# led_board_robot_vs_v2.net
KiCad netlist of a schematic drawn in EAGLE
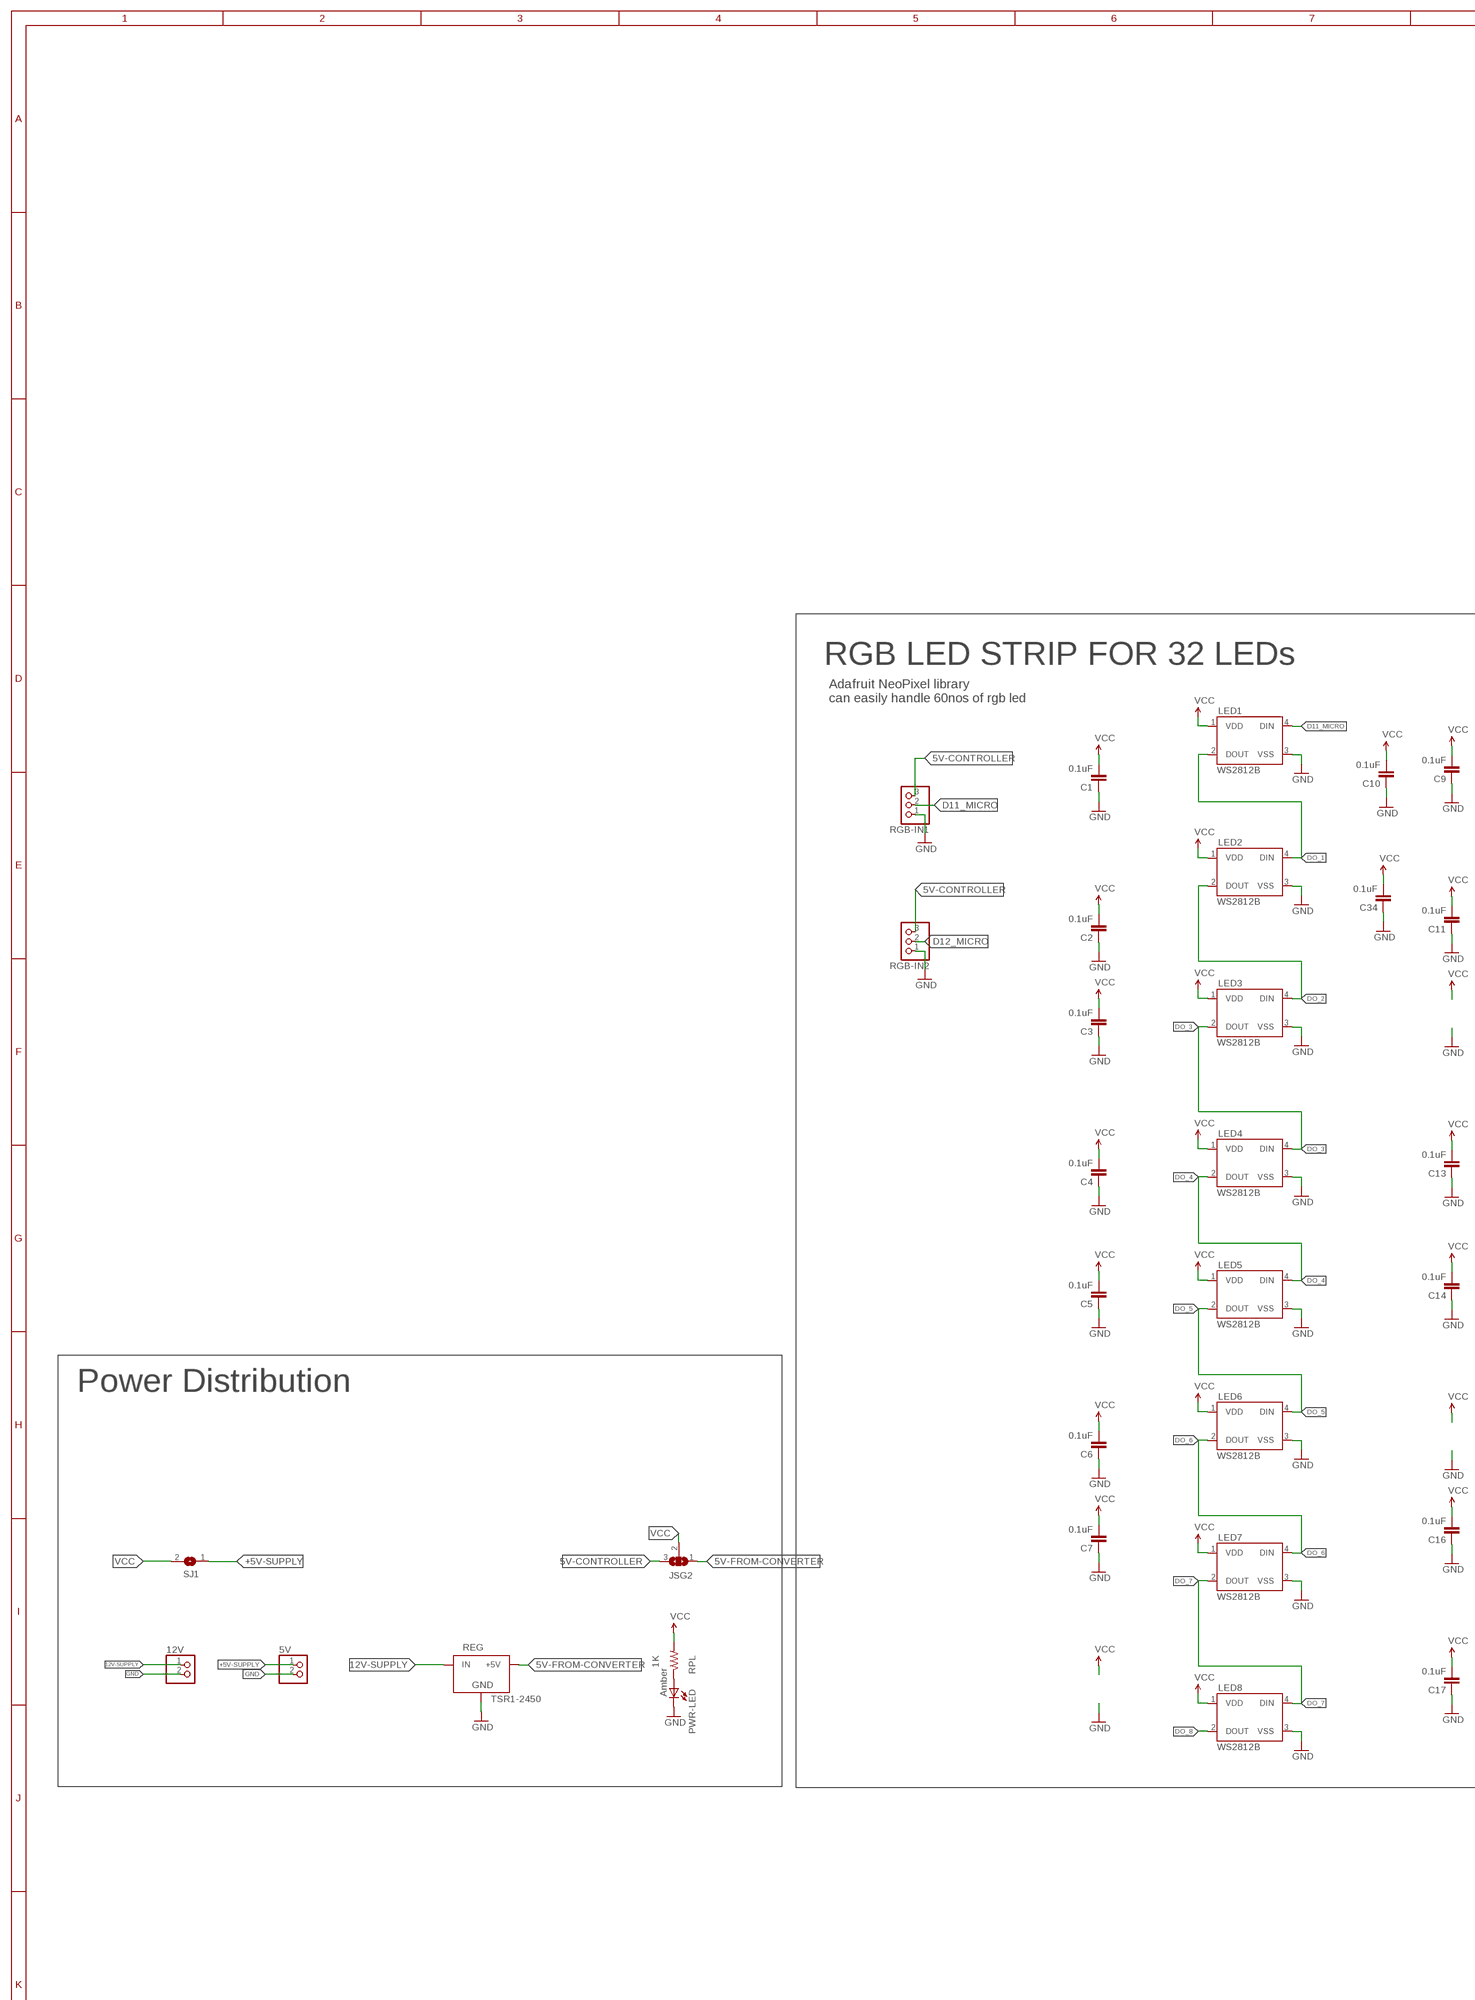
[diagram p0: schematic, sheet 1, part 1 of 3]
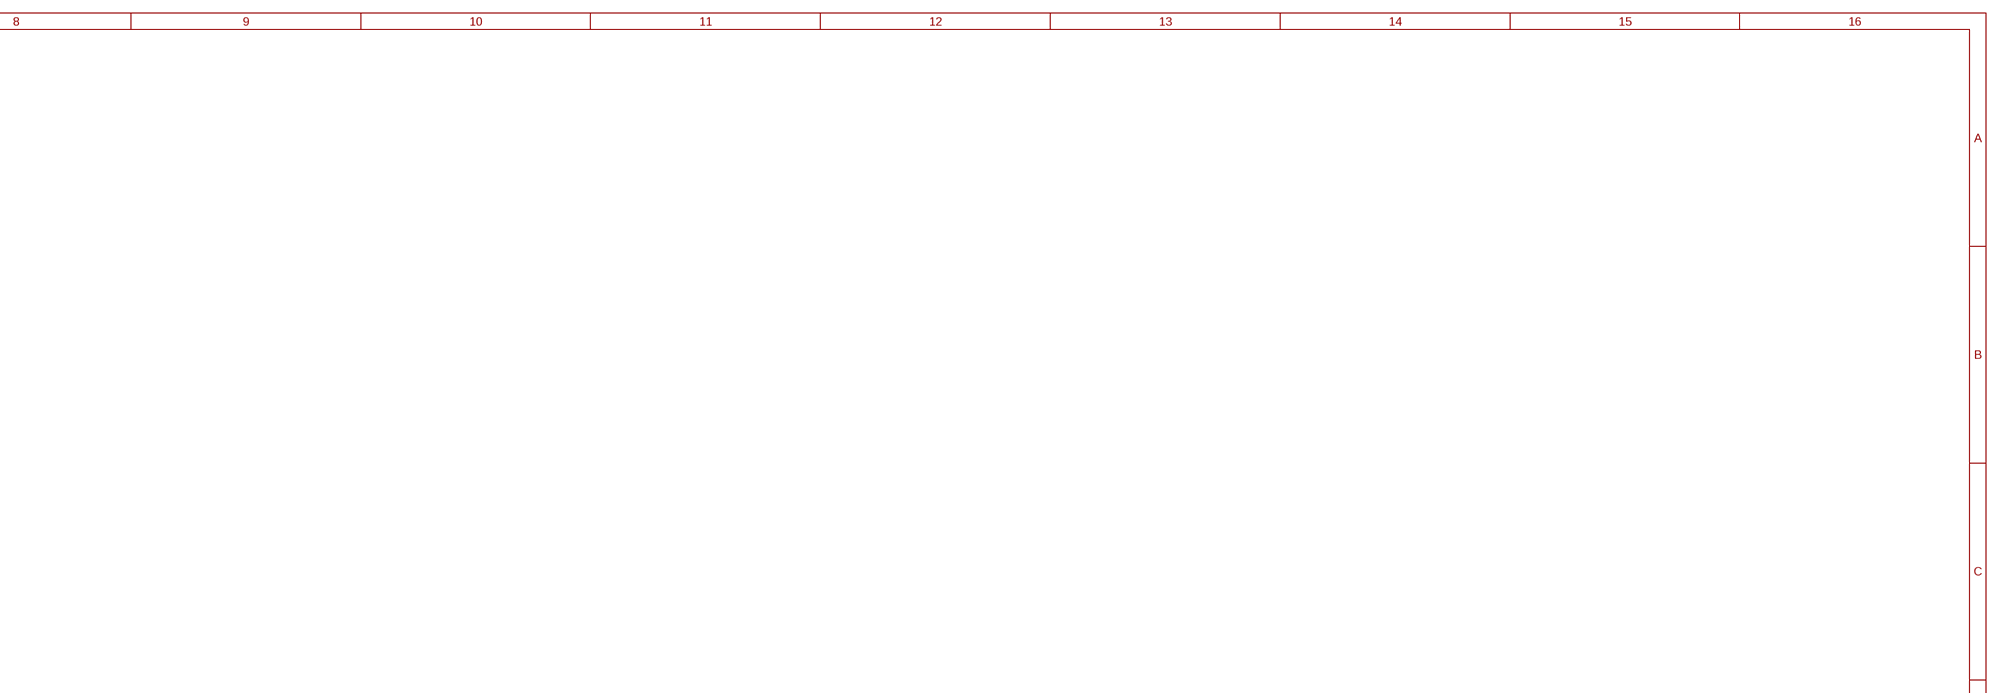
[diagram p1: schematic, sheet 1, part 2 of 3]
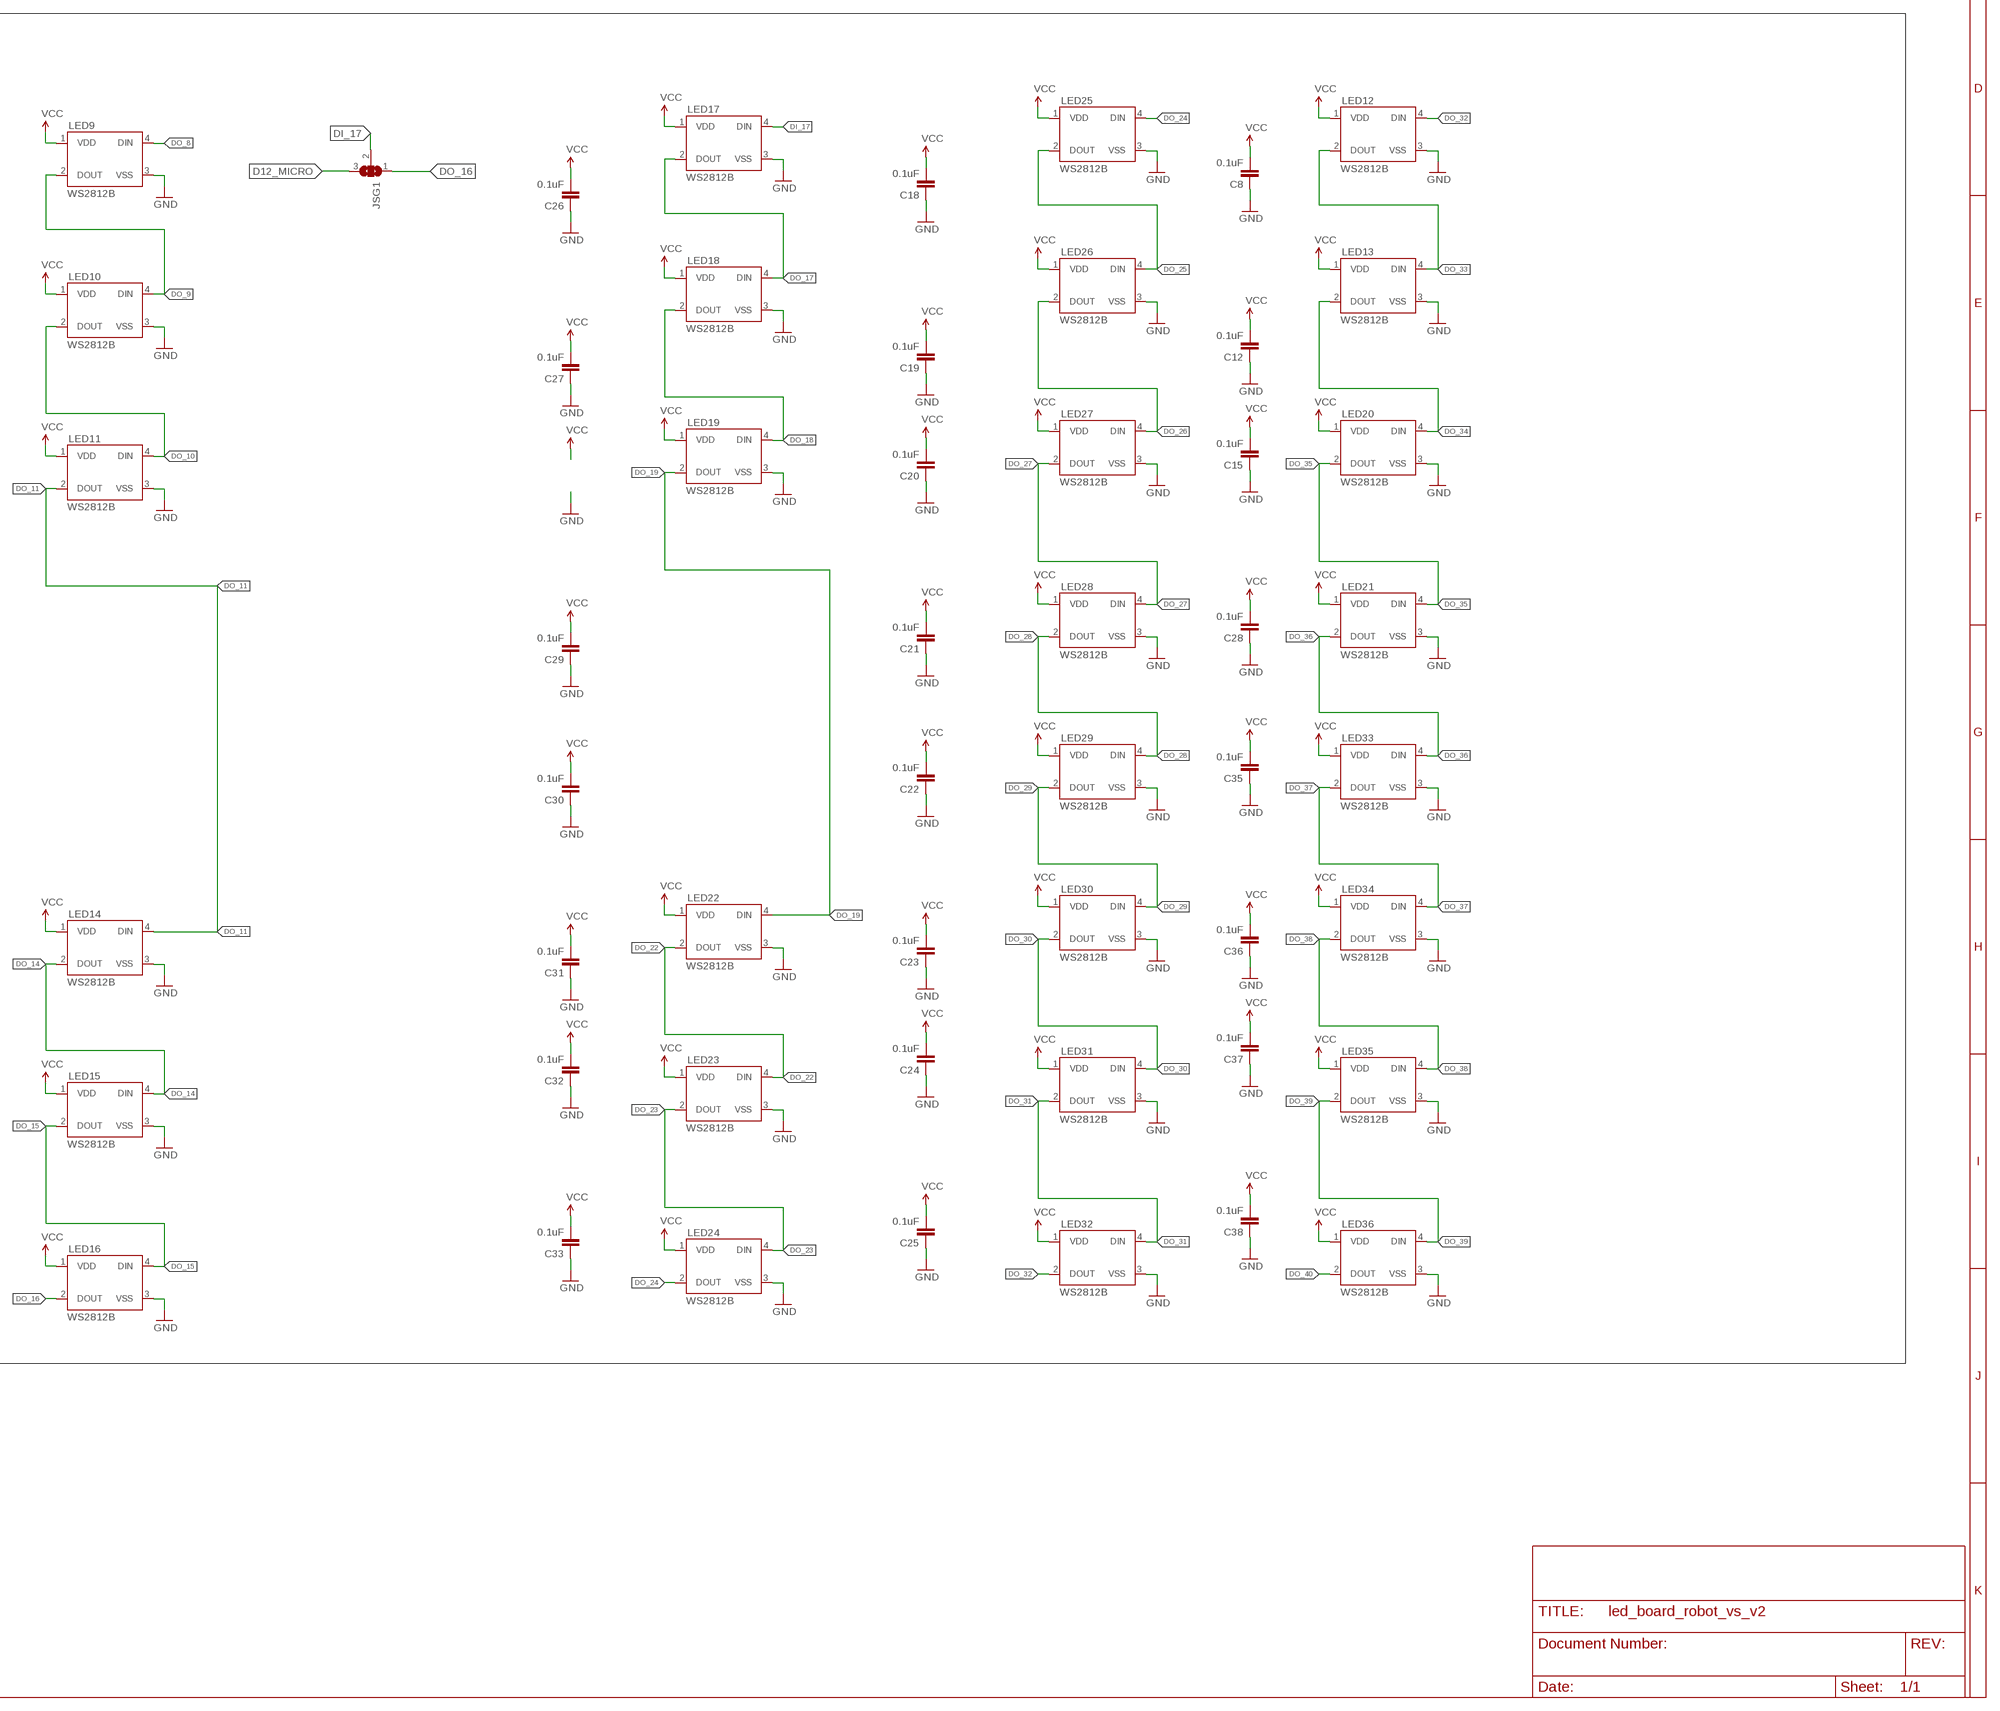
[diagram p2: schematic, sheet 1, part 3 of 3]

(export (version "E")
  (design (tool "Eeschema 10.0.6"))
  (components
    (comp (ref "5V")
      (value "PINHD-1X2")
      (footprint "eagle-import:1X02")
      (libsource (lib "eagle-import") (part "PINHD-1X2"))
    )
    (comp (ref "12V")
      (value "PINHD-1X2")
      (footprint "eagle-import:1X02")
      (libsource (lib "eagle-import") (part "PINHD-1X2"))
    )
    (comp (ref "C1")
      (value "0.1uF")
      (footprint "eagle-import:0603-CAP")
      (libsource (lib "eagle-import") (part "CAP0603-CAP"))
    )
    (comp (ref "C2")
      (value "0.1uF")
      (footprint "eagle-import:0603-CAP")
      (libsource (lib "eagle-import") (part "CAP0603-CAP"))
    )
    (comp (ref "C3")
      (value "0.1uF")
      (footprint "eagle-import:0603-CAP")
      (libsource (lib "eagle-import") (part "CAP0603-CAP"))
    )
    (comp (ref "C4")
      (value "0.1uF")
      (footprint "eagle-import:0603-CAP")
      (libsource (lib "eagle-import") (part "CAP0603-CAP"))
    )
    (comp (ref "C5")
      (value "0.1uF")
      (footprint "eagle-import:0603-CAP")
      (libsource (lib "eagle-import") (part "CAP0603-CAP"))
    )
    (comp (ref "C6")
      (value "0.1uF")
      (footprint "eagle-import:0603-CAP")
      (libsource (lib "eagle-import") (part "CAP0603-CAP"))
    )
    (comp (ref "C7")
      (value "0.1uF")
      (footprint "eagle-import:0603-CAP")
      (libsource (lib "eagle-import") (part "CAP0603-CAP"))
    )
    (comp (ref "C8")
      (value "0.1uF")
      (footprint "eagle-import:0603-CAP")
      (libsource (lib "eagle-import") (part "CAP0603-CAP"))
    )
    (comp (ref "C9")
      (value "0.1uF")
      (footprint "eagle-import:0603-CAP")
      (libsource (lib "eagle-import") (part "CAP0603-CAP"))
    )
    (comp (ref "C10")
      (value "0.1uF")
      (footprint "eagle-import:0603-CAP")
      (libsource (lib "eagle-import") (part "CAP0603-CAP"))
    )
    (comp (ref "C11")
      (value "0.1uF")
      (footprint "eagle-import:0603-CAP")
      (libsource (lib "eagle-import") (part "CAP0603-CAP"))
    )
    (comp (ref "C12")
      (value "0.1uF")
      (footprint "eagle-import:0603-CAP")
      (libsource (lib "eagle-import") (part "CAP0603-CAP"))
    )
    (comp (ref "C13")
      (value "0.1uF")
      (footprint "eagle-import:0603-CAP")
      (libsource (lib "eagle-import") (part "CAP0603-CAP"))
    )
    (comp (ref "C14")
      (value "0.1uF")
      (footprint "eagle-import:0603-CAP")
      (libsource (lib "eagle-import") (part "CAP0603-CAP"))
    )
    (comp (ref "C15")
      (value "0.1uF")
      (footprint "eagle-import:0603-CAP")
      (libsource (lib "eagle-import") (part "CAP0603-CAP"))
    )
    (comp (ref "C16")
      (value "0.1uF")
      (footprint "eagle-import:0603-CAP")
      (libsource (lib "eagle-import") (part "CAP0603-CAP"))
    )
    (comp (ref "C17")
      (value "0.1uF")
      (footprint "eagle-import:0603-CAP")
      (libsource (lib "eagle-import") (part "CAP0603-CAP"))
    )
    (comp (ref "C18")
      (value "0.1uF")
      (footprint "eagle-import:0603-CAP")
      (libsource (lib "eagle-import") (part "CAP0603-CAP"))
    )
    (comp (ref "C19")
      (value "0.1uF")
      (footprint "eagle-import:0603-CAP")
      (libsource (lib "eagle-import") (part "CAP0603-CAP"))
    )
    (comp (ref "C20")
      (value "0.1uF")
      (footprint "eagle-import:0603-CAP")
      (libsource (lib "eagle-import") (part "CAP0603-CAP"))
    )
    (comp (ref "C21")
      (value "0.1uF")
      (footprint "eagle-import:0603-CAP")
      (libsource (lib "eagle-import") (part "CAP0603-CAP"))
    )
    (comp (ref "C22")
      (value "0.1uF")
      (footprint "eagle-import:0603-CAP")
      (libsource (lib "eagle-import") (part "CAP0603-CAP"))
    )
    (comp (ref "C23")
      (value "0.1uF")
      (footprint "eagle-import:0603-CAP")
      (libsource (lib "eagle-import") (part "CAP0603-CAP"))
    )
    (comp (ref "C24")
      (value "0.1uF")
      (footprint "eagle-import:0603-CAP")
      (libsource (lib "eagle-import") (part "CAP0603-CAP"))
    )
    (comp (ref "C25")
      (value "0.1uF")
      (footprint "eagle-import:0603-CAP")
      (libsource (lib "eagle-import") (part "CAP0603-CAP"))
    )
    (comp (ref "C26")
      (value "0.1uF")
      (footprint "eagle-import:0603-CAP")
      (libsource (lib "eagle-import") (part "CAP0603-CAP"))
    )
    (comp (ref "C27")
      (value "0.1uF")
      (footprint "eagle-import:0603-CAP")
      (libsource (lib "eagle-import") (part "CAP0603-CAP"))
    )
    (comp (ref "C28")
      (value "0.1uF")
      (footprint "eagle-import:0603-CAP")
      (libsource (lib "eagle-import") (part "CAP0603-CAP"))
    )
    (comp (ref "C29")
      (value "0.1uF")
      (footprint "eagle-import:0603-CAP")
      (libsource (lib "eagle-import") (part "CAP0603-CAP"))
    )
    (comp (ref "C30")
      (value "0.1uF")
      (footprint "eagle-import:0603-CAP")
      (libsource (lib "eagle-import") (part "CAP0603-CAP"))
    )
    (comp (ref "C31")
      (value "0.1uF")
      (footprint "eagle-import:0603-CAP")
      (libsource (lib "eagle-import") (part "CAP0603-CAP"))
    )
    (comp (ref "C32")
      (value "0.1uF")
      (footprint "eagle-import:0603-CAP")
      (libsource (lib "eagle-import") (part "CAP0603-CAP"))
    )
    (comp (ref "C33")
      (value "0.1uF")
      (footprint "eagle-import:0603-CAP")
      (libsource (lib "eagle-import") (part "CAP0603-CAP"))
    )
    (comp (ref "C34")
      (value "0.1uF")
      (footprint "eagle-import:0603-CAP")
      (libsource (lib "eagle-import") (part "CAP0603-CAP"))
    )
    (comp (ref "C35")
      (value "0.1uF")
      (footprint "eagle-import:0603-CAP")
      (libsource (lib "eagle-import") (part "CAP0603-CAP"))
    )
    (comp (ref "C36")
      (value "0.1uF")
      (footprint "eagle-import:0603-CAP")
      (libsource (lib "eagle-import") (part "CAP0603-CAP"))
    )
    (comp (ref "C37")
      (value "0.1uF")
      (footprint "eagle-import:0603-CAP")
      (libsource (lib "eagle-import") (part "CAP0603-CAP"))
    )
    (comp (ref "C38")
      (value "0.1uF")
      (footprint "eagle-import:0603-CAP")
      (libsource (lib "eagle-import") (part "CAP0603-CAP"))
    )
    (comp (ref "JSG1")
      (value "SJ2WW")
      (footprint "eagle-import:SJ_2W")
      (libsource (lib "eagle-import") (part "SJ2WW"))
    )
    (comp (ref "JSG2")
      (value "SJ2WW")
      (footprint "eagle-import:SJ_2W")
      (libsource (lib "eagle-import") (part "SJ2WW"))
    )
    (comp (ref "LED1")
      (value "WS2812B")
      (footprint "eagle-import:WS2812B")
      (libsource (lib "eagle-import") (part "WS2812B"))
    )
    (comp (ref "LED2")
      (value "WS2812B")
      (footprint "eagle-import:WS2812B")
      (libsource (lib "eagle-import") (part "WS2812B"))
    )
    (comp (ref "LED3")
      (value "WS2812B")
      (footprint "eagle-import:WS2812B")
      (libsource (lib "eagle-import") (part "WS2812B"))
    )
    (comp (ref "LED4")
      (value "WS2812B")
      (footprint "eagle-import:WS2812B")
      (libsource (lib "eagle-import") (part "WS2812B"))
    )
    (comp (ref "LED5")
      (value "WS2812B")
      (footprint "eagle-import:WS2812B")
      (libsource (lib "eagle-import") (part "WS2812B"))
    )
    (comp (ref "LED6")
      (value "WS2812B")
      (footprint "eagle-import:WS2812B")
      (libsource (lib "eagle-import") (part "WS2812B"))
    )
    (comp (ref "LED7")
      (value "WS2812B")
      (footprint "eagle-import:WS2812B")
      (libsource (lib "eagle-import") (part "WS2812B"))
    )
    (comp (ref "LED8")
      (value "WS2812B")
      (footprint "eagle-import:WS2812B")
      (libsource (lib "eagle-import") (part "WS2812B"))
    )
    (comp (ref "LED9")
      (value "WS2812B")
      (footprint "eagle-import:WS2812B")
      (libsource (lib "eagle-import") (part "WS2812B"))
    )
    (comp (ref "LED10")
      (value "WS2812B")
      (footprint "eagle-import:WS2812B")
      (libsource (lib "eagle-import") (part "WS2812B"))
    )
    (comp (ref "LED11")
      (value "WS2812B")
      (footprint "eagle-import:WS2812B")
      (libsource (lib "eagle-import") (part "WS2812B"))
    )
    (comp (ref "LED12")
      (value "WS2812B")
      (footprint "eagle-import:WS2812B")
      (libsource (lib "eagle-import") (part "WS2812B"))
    )
    (comp (ref "LED13")
      (value "WS2812B")
      (footprint "eagle-import:WS2812B")
      (libsource (lib "eagle-import") (part "WS2812B"))
    )
    (comp (ref "LED14")
      (value "WS2812B")
      (footprint "eagle-import:WS2812B")
      (libsource (lib "eagle-import") (part "WS2812B"))
    )
    (comp (ref "LED15")
      (value "WS2812B")
      (footprint "eagle-import:WS2812B")
      (libsource (lib "eagle-import") (part "WS2812B"))
    )
    (comp (ref "LED16")
      (value "WS2812B")
      (footprint "eagle-import:WS2812B")
      (libsource (lib "eagle-import") (part "WS2812B"))
    )
    (comp (ref "LED17")
      (value "WS2812B")
      (footprint "eagle-import:WS2812B")
      (libsource (lib "eagle-import") (part "WS2812B"))
    )
    (comp (ref "LED18")
      (value "WS2812B")
      (footprint "eagle-import:WS2812B")
      (libsource (lib "eagle-import") (part "WS2812B"))
    )
    (comp (ref "LED19")
      (value "WS2812B")
      (footprint "eagle-import:WS2812B")
      (libsource (lib "eagle-import") (part "WS2812B"))
    )
    (comp (ref "LED20")
      (value "WS2812B")
      (footprint "eagle-import:WS2812B")
      (libsource (lib "eagle-import") (part "WS2812B"))
    )
    (comp (ref "LED21")
      (value "WS2812B")
      (footprint "eagle-import:WS2812B")
      (libsource (lib "eagle-import") (part "WS2812B"))
    )
    (comp (ref "LED22")
      (value "WS2812B")
      (footprint "eagle-import:WS2812B")
      (libsource (lib "eagle-import") (part "WS2812B"))
    )
    (comp (ref "LED23")
      (value "WS2812B")
      (footprint "eagle-import:WS2812B")
      (libsource (lib "eagle-import") (part "WS2812B"))
    )
    (comp (ref "LED24")
      (value "WS2812B")
      (footprint "eagle-import:WS2812B")
      (libsource (lib "eagle-import") (part "WS2812B"))
    )
    (comp (ref "LED25")
      (value "WS2812B")
      (footprint "eagle-import:WS2812B")
      (libsource (lib "eagle-import") (part "WS2812B"))
    )
    (comp (ref "LED26")
      (value "WS2812B")
      (footprint "eagle-import:WS2812B")
      (libsource (lib "eagle-import") (part "WS2812B"))
    )
    (comp (ref "LED27")
      (value "WS2812B")
      (footprint "eagle-import:WS2812B")
      (libsource (lib "eagle-import") (part "WS2812B"))
    )
    (comp (ref "LED28")
      (value "WS2812B")
      (footprint "eagle-import:WS2812B")
      (libsource (lib "eagle-import") (part "WS2812B"))
    )
    (comp (ref "LED29")
      (value "WS2812B")
      (footprint "eagle-import:WS2812B")
      (libsource (lib "eagle-import") (part "WS2812B"))
    )
    (comp (ref "LED30")
      (value "WS2812B")
      (footprint "eagle-import:WS2812B")
      (libsource (lib "eagle-import") (part "WS2812B"))
    )
    (comp (ref "LED31")
      (value "WS2812B")
      (footprint "eagle-import:WS2812B")
      (libsource (lib "eagle-import") (part "WS2812B"))
    )
    (comp (ref "LED32")
      (value "WS2812B")
      (footprint "eagle-import:WS2812B")
      (libsource (lib "eagle-import") (part "WS2812B"))
    )
    (comp (ref "LED33")
      (value "WS2812B")
      (footprint "eagle-import:WS2812B")
      (libsource (lib "eagle-import") (part "WS2812B"))
    )
    (comp (ref "LED34")
      (value "WS2812B")
      (footprint "eagle-import:WS2812B")
      (libsource (lib "eagle-import") (part "WS2812B"))
    )
    (comp (ref "LED35")
      (value "WS2812B")
      (footprint "eagle-import:WS2812B")
      (libsource (lib "eagle-import") (part "WS2812B"))
    )
    (comp (ref "LED36")
      (value "WS2812B")
      (footprint "eagle-import:WS2812B")
      (libsource (lib "eagle-import") (part "WS2812B"))
    )
    (comp (ref "PWR-LED")
      (value "Amber")
      (footprint "eagle-import:LED-0603")
      (libsource (lib "eagle-import") (part "LED0603"))
    )
    (comp (ref "REG")
      (value "TSR1-2450")
      (footprint "eagle-import:TSR-1")
      (libsource (lib "eagle-import") (part "TSR1-2450"))
    )
    (comp (ref "RGB-IN1")
      (value "PINHD-1X3")
      (footprint "eagle-import:1X03")
      (libsource (lib "eagle-import") (part "PINHD-1X3"))
    )
    (comp (ref "RGB-IN2")
      (value "PINHD-1X3")
      (footprint "eagle-import:1X03")
      (libsource (lib "eagle-import") (part "PINHD-1X3"))
    )
    (comp (ref "RPL")
      (value "1K")
      (footprint "eagle-import:0603-RES")
      (libsource (lib "eagle-import") (part "RESISTOR0603-RES"))
    )
    (comp (ref "SJ1")
      (value "SJW")
      (footprint "eagle-import:SJW")
      (libsource (lib "eagle-import") (part "SJW"))
    )
  )
  (nets
    (net (code "1") (name "+5V-SUPPLY") (class "Default")
      (node (ref "5V") (pin "1") (pinfunction "1_1") (pintype "passive"))
      (node (ref "SJ1") (pin "1") (pinfunction "1_1") (pintype "passive"))
    )
    (net (code "2") (name "5V-CONTROLLER") (class "Default")
      (node (ref "JSG2") (pin "3") (pinfunction "3_3") (pintype "passive"))
      (node (ref "RGB-IN1") (pin "3") (pinfunction "3_3") (pintype "passive"))
      (node (ref "RGB-IN2") (pin "3") (pinfunction "3_3") (pintype "passive"))
    )
    (net (code "3") (name "5V-FROM-CONVERTER") (class "Default")
      (node (ref "JSG2") (pin "1") (pinfunction "1_1") (pintype "passive"))
      (node (ref "REG") (pin "3") (pinfunction "+5V_3") (pintype "power_in"))
    )
    (net (code "4") (name "12V-SUPPLY") (class "Default")
      (node (ref "12V") (pin "1") (pinfunction "1_1") (pintype "passive"))
      (node (ref "REG") (pin "1") (pinfunction "IN_1") (pintype "power_in"))
    )
    (net (code "5") (name "D11_MICRO") (class "Default")
      (node (ref "LED1") (pin "4") (pinfunction "DIN_4") (pintype "input"))
      (node (ref "RGB-IN1") (pin "2") (pinfunction "2_2") (pintype "passive"))
    )
    (net (code "6") (name "D12_MICRO") (class "Default")
      (node (ref "JSG1") (pin "3") (pinfunction "3_3") (pintype "passive"))
      (node (ref "RGB-IN2") (pin "2") (pinfunction "2_2") (pintype "passive"))
    )
    (net (code "7") (name "DI_17") (class "Default")
      (node (ref "JSG1") (pin "2") (pinfunction "2_2") (pintype "passive"))
      (node (ref "LED17") (pin "4") (pinfunction "DIN_4") (pintype "input"))
    )
    (net (code "8") (name "DO_1") (class "Default")
      (node (ref "LED1") (pin "2") (pinfunction "DOUT_2") (pintype "output"))
      (node (ref "LED2") (pin "4") (pinfunction "DIN_4") (pintype "input"))
    )
    (net (code "9") (name "DO_2") (class "Default")
      (node (ref "LED2") (pin "2") (pinfunction "DOUT_2") (pintype "output"))
      (node (ref "LED3") (pin "4") (pinfunction "DIN_4") (pintype "input"))
    )
    (net (code "10") (name "DO_3") (class "Default")
      (node (ref "LED3") (pin "2") (pinfunction "DOUT_2") (pintype "output"))
      (node (ref "LED4") (pin "4") (pinfunction "DIN_4") (pintype "input"))
    )
    (net (code "11") (name "DO_4") (class "Default")
      (node (ref "LED4") (pin "2") (pinfunction "DOUT_2") (pintype "output"))
      (node (ref "LED5") (pin "4") (pinfunction "DIN_4") (pintype "input"))
    )
    (net (code "12") (name "DO_5") (class "Default")
      (node (ref "LED5") (pin "2") (pinfunction "DOUT_2") (pintype "output"))
      (node (ref "LED6") (pin "4") (pinfunction "DIN_4") (pintype "input"))
    )
    (net (code "13") (name "DO_6") (class "Default")
      (node (ref "LED6") (pin "2") (pinfunction "DOUT_2") (pintype "output"))
      (node (ref "LED7") (pin "4") (pinfunction "DIN_4") (pintype "input"))
    )
    (net (code "14") (name "DO_7") (class "Default")
      (node (ref "LED7") (pin "2") (pinfunction "DOUT_2") (pintype "output"))
      (node (ref "LED8") (pin "4") (pinfunction "DIN_4") (pintype "input"))
    )
    (net (code "15") (name "DO_8") (class "Default")
      (node (ref "LED8") (pin "2") (pinfunction "DOUT_2") (pintype "output"))
      (node (ref "LED9") (pin "4") (pinfunction "DIN_4") (pintype "input"))
    )
    (net (code "16") (name "DO_9") (class "Default")
      (node (ref "LED10") (pin "4") (pinfunction "DIN_4") (pintype "input"))
      (node (ref "LED9") (pin "2") (pinfunction "DOUT_2") (pintype "output"))
    )
    (net (code "17") (name "DO_10") (class "Default")
      (node (ref "LED10") (pin "2") (pinfunction "DOUT_2") (pintype "output"))
      (node (ref "LED11") (pin "4") (pinfunction "DIN_4") (pintype "input"))
    )
    (net (code "18") (name "DO_11") (class "Default")
      (node (ref "LED11") (pin "2") (pinfunction "DOUT_2") (pintype "output"))
      (node (ref "LED14") (pin "4") (pinfunction "DIN_4") (pintype "input"))
    )
    (net (code "19") (name "DO_14") (class "Default")
      (node (ref "LED14") (pin "2") (pinfunction "DOUT_2") (pintype "output"))
      (node (ref "LED15") (pin "4") (pinfunction "DIN_4") (pintype "input"))
    )
    (net (code "20") (name "DO_15") (class "Default")
      (node (ref "LED15") (pin "2") (pinfunction "DOUT_2") (pintype "output"))
      (node (ref "LED16") (pin "4") (pinfunction "DIN_4") (pintype "input"))
    )
    (net (code "21") (name "DO_16") (class "Default")
      (node (ref "JSG1") (pin "1") (pinfunction "1_1") (pintype "passive"))
      (node (ref "LED16") (pin "2") (pinfunction "DOUT_2") (pintype "output"))
    )
    (net (code "22") (name "DO_17") (class "Default")
      (node (ref "LED17") (pin "2") (pinfunction "DOUT_2") (pintype "output"))
      (node (ref "LED18") (pin "4") (pinfunction "DIN_4") (pintype "input"))
    )
    (net (code "23") (name "DO_18") (class "Default")
      (node (ref "LED18") (pin "2") (pinfunction "DOUT_2") (pintype "output"))
      (node (ref "LED19") (pin "4") (pinfunction "DIN_4") (pintype "input"))
    )
    (net (code "24") (name "DO_19") (class "Default")
      (node (ref "LED19") (pin "2") (pinfunction "DOUT_2") (pintype "output"))
      (node (ref "LED22") (pin "4") (pinfunction "DIN_4") (pintype "input"))
    )
    (net (code "25") (name "DO_22") (class "Default")
      (node (ref "LED22") (pin "2") (pinfunction "DOUT_2") (pintype "output"))
      (node (ref "LED23") (pin "4") (pinfunction "DIN_4") (pintype "input"))
    )
    (net (code "26") (name "DO_23") (class "Default")
      (node (ref "LED23") (pin "2") (pinfunction "DOUT_2") (pintype "output"))
      (node (ref "LED24") (pin "4") (pinfunction "DIN_4") (pintype "input"))
    )
    (net (code "27") (name "DO_24") (class "Default")
      (node (ref "LED24") (pin "2") (pinfunction "DOUT_2") (pintype "output"))
      (node (ref "LED25") (pin "4") (pinfunction "DIN_4") (pintype "input"))
    )
    (net (code "28") (name "DO_25") (class "Default")
      (node (ref "LED25") (pin "2") (pinfunction "DOUT_2") (pintype "output"))
      (node (ref "LED26") (pin "4") (pinfunction "DIN_4") (pintype "input"))
    )
    (net (code "29") (name "DO_26") (class "Default")
      (node (ref "LED26") (pin "2") (pinfunction "DOUT_2") (pintype "output"))
      (node (ref "LED27") (pin "4") (pinfunction "DIN_4") (pintype "input"))
    )
    (net (code "30") (name "DO_27") (class "Default")
      (node (ref "LED27") (pin "2") (pinfunction "DOUT_2") (pintype "output"))
      (node (ref "LED28") (pin "4") (pinfunction "DIN_4") (pintype "input"))
    )
    (net (code "31") (name "DO_28") (class "Default")
      (node (ref "LED28") (pin "2") (pinfunction "DOUT_2") (pintype "output"))
      (node (ref "LED29") (pin "4") (pinfunction "DIN_4") (pintype "input"))
    )
    (net (code "32") (name "DO_29") (class "Default")
      (node (ref "LED29") (pin "2") (pinfunction "DOUT_2") (pintype "output"))
      (node (ref "LED30") (pin "4") (pinfunction "DIN_4") (pintype "input"))
    )
    (net (code "33") (name "DO_30") (class "Default")
      (node (ref "LED30") (pin "2") (pinfunction "DOUT_2") (pintype "output"))
      (node (ref "LED31") (pin "4") (pinfunction "DIN_4") (pintype "input"))
    )
    (net (code "34") (name "DO_31") (class "Default")
      (node (ref "LED31") (pin "2") (pinfunction "DOUT_2") (pintype "output"))
      (node (ref "LED32") (pin "4") (pinfunction "DIN_4") (pintype "input"))
    )
    (net (code "35") (name "DO_32") (class "Default")
      (node (ref "LED12") (pin "4") (pinfunction "DIN_4") (pintype "input"))
      (node (ref "LED32") (pin "2") (pinfunction "DOUT_2") (pintype "output"))
    )
    (net (code "36") (name "DO_33") (class "Default")
      (node (ref "LED12") (pin "2") (pinfunction "DOUT_2") (pintype "output"))
      (node (ref "LED13") (pin "4") (pinfunction "DIN_4") (pintype "input"))
    )
    (net (code "37") (name "DO_34") (class "Default")
      (node (ref "LED13") (pin "2") (pinfunction "DOUT_2") (pintype "output"))
      (node (ref "LED20") (pin "4") (pinfunction "DIN_4") (pintype "input"))
    )
    (net (code "38") (name "DO_35") (class "Default")
      (node (ref "LED20") (pin "2") (pinfunction "DOUT_2") (pintype "output"))
      (node (ref "LED21") (pin "4") (pinfunction "DIN_4") (pintype "input"))
    )
    (net (code "39") (name "DO_36") (class "Default")
      (node (ref "LED21") (pin "2") (pinfunction "DOUT_2") (pintype "output"))
      (node (ref "LED33") (pin "4") (pinfunction "DIN_4") (pintype "input"))
    )
    (net (code "40") (name "DO_37") (class "Default")
      (node (ref "LED33") (pin "2") (pinfunction "DOUT_2") (pintype "output"))
      (node (ref "LED34") (pin "4") (pinfunction "DIN_4") (pintype "input"))
    )
    (net (code "41") (name "DO_38") (class "Default")
      (node (ref "LED34") (pin "2") (pinfunction "DOUT_2") (pintype "output"))
      (node (ref "LED35") (pin "4") (pinfunction "DIN_4") (pintype "input"))
    )
    (net (code "42") (name "DO_39") (class "Default")
      (node (ref "LED35") (pin "2") (pinfunction "DOUT_2") (pintype "output"))
      (node (ref "LED36") (pin "4") (pinfunction "DIN_4") (pintype "input"))
    )
    (net (code "43") (name "DO_40") (class "Default")
      (node (ref "LED36") (pin "2") (pinfunction "DOUT_2") (pintype "output"))
    )
    (net (code "44") (name "GND") (class "Default")
      (node (ref "12V") (pin "2") (pinfunction "2_2") (pintype "passive"))
      (node (ref "5V") (pin "2") (pinfunction "2_2") (pintype "passive"))
      (node (ref "C1") (pin "1") (pinfunction "1_1") (pintype "passive"))
      (node (ref "C10") (pin "1") (pinfunction "1_1") (pintype "passive"))
      (node (ref "C11") (pin "1") (pinfunction "1_1") (pintype "passive"))
      (node (ref "C12") (pin "1") (pinfunction "1_1") (pintype "passive"))
      (node (ref "C13") (pin "1") (pinfunction "1_1") (pintype "passive"))
      (node (ref "C14") (pin "1") (pinfunction "1_1") (pintype "passive"))
      (node (ref "C15") (pin "1") (pinfunction "1_1") (pintype "passive"))
      (node (ref "C16") (pin "1") (pinfunction "1_1") (pintype "passive"))
      (node (ref "C17") (pin "1") (pinfunction "1_1") (pintype "passive"))
      (node (ref "C18") (pin "1") (pinfunction "1_1") (pintype "passive"))
      (node (ref "C19") (pin "1") (pinfunction "1_1") (pintype "passive"))
      (node (ref "C2") (pin "1") (pinfunction "1_1") (pintype "passive"))
      (node (ref "C20") (pin "1") (pinfunction "1_1") (pintype "passive"))
      (node (ref "C21") (pin "1") (pinfunction "1_1") (pintype "passive"))
      (node (ref "C22") (pin "1") (pinfunction "1_1") (pintype "passive"))
      (node (ref "C23") (pin "1") (pinfunction "1_1") (pintype "passive"))
      (node (ref "C24") (pin "1") (pinfunction "1_1") (pintype "passive"))
      (node (ref "C25") (pin "1") (pinfunction "1_1") (pintype "passive"))
      (node (ref "C26") (pin "1") (pinfunction "1_1") (pintype "passive"))
      (node (ref "C27") (pin "1") (pinfunction "1_1") (pintype "passive"))
      (node (ref "C28") (pin "1") (pinfunction "1_1") (pintype "passive"))
      (node (ref "C29") (pin "1") (pinfunction "1_1") (pintype "passive"))
      (node (ref "C3") (pin "1") (pinfunction "1_1") (pintype "passive"))
      (node (ref "C30") (pin "1") (pinfunction "1_1") (pintype "passive"))
      (node (ref "C31") (pin "1") (pinfunction "1_1") (pintype "passive"))
      (node (ref "C32") (pin "1") (pinfunction "1_1") (pintype "passive"))
      (node (ref "C33") (pin "1") (pinfunction "1_1") (pintype "passive"))
      (node (ref "C34") (pin "1") (pinfunction "1_1") (pintype "passive"))
      (node (ref "C35") (pin "1") (pinfunction "1_1") (pintype "passive"))
      (node (ref "C36") (pin "1") (pinfunction "1_1") (pintype "passive"))
      (node (ref "C37") (pin "1") (pinfunction "1_1") (pintype "passive"))
      (node (ref "C38") (pin "1") (pinfunction "1_1") (pintype "passive"))
      (node (ref "C4") (pin "1") (pinfunction "1_1") (pintype "passive"))
      (node (ref "C5") (pin "1") (pinfunction "1_1") (pintype "passive"))
      (node (ref "C6") (pin "1") (pinfunction "1_1") (pintype "passive"))
      (node (ref "C7") (pin "1") (pinfunction "1_1") (pintype "passive"))
      (node (ref "C8") (pin "1") (pinfunction "1_1") (pintype "passive"))
      (node (ref "C9") (pin "1") (pinfunction "1_1") (pintype "passive"))
      (node (ref "LED1") (pin "3") (pinfunction "VSS_3") (pintype "power_in"))
      (node (ref "LED10") (pin "3") (pinfunction "VSS_3") (pintype "power_in"))
      (node (ref "LED11") (pin "3") (pinfunction "VSS_3") (pintype "power_in"))
      (node (ref "LED12") (pin "3") (pinfunction "VSS_3") (pintype "power_in"))
      (node (ref "LED13") (pin "3") (pinfunction "VSS_3") (pintype "power_in"))
      (node (ref "LED14") (pin "3") (pinfunction "VSS_3") (pintype "power_in"))
      (node (ref "LED15") (pin "3") (pinfunction "VSS_3") (pintype "power_in"))
      (node (ref "LED16") (pin "3") (pinfunction "VSS_3") (pintype "power_in"))
      (node (ref "LED17") (pin "3") (pinfunction "VSS_3") (pintype "power_in"))
      (node (ref "LED18") (pin "3") (pinfunction "VSS_3") (pintype "power_in"))
      (node (ref "LED19") (pin "3") (pinfunction "VSS_3") (pintype "power_in"))
      (node (ref "LED2") (pin "3") (pinfunction "VSS_3") (pintype "power_in"))
      (node (ref "LED20") (pin "3") (pinfunction "VSS_3") (pintype "power_in"))
      (node (ref "LED21") (pin "3") (pinfunction "VSS_3") (pintype "power_in"))
      (node (ref "LED22") (pin "3") (pinfunction "VSS_3") (pintype "power_in"))
      (node (ref "LED23") (pin "3") (pinfunction "VSS_3") (pintype "power_in"))
      (node (ref "LED24") (pin "3") (pinfunction "VSS_3") (pintype "power_in"))
      (node (ref "LED25") (pin "3") (pinfunction "VSS_3") (pintype "power_in"))
      (node (ref "LED26") (pin "3") (pinfunction "VSS_3") (pintype "power_in"))
      (node (ref "LED27") (pin "3") (pinfunction "VSS_3") (pintype "power_in"))
      (node (ref "LED28") (pin "3") (pinfunction "VSS_3") (pintype "power_in"))
      (node (ref "LED29") (pin "3") (pinfunction "VSS_3") (pintype "power_in"))
      (node (ref "LED3") (pin "3") (pinfunction "VSS_3") (pintype "power_in"))
      (node (ref "LED30") (pin "3") (pinfunction "VSS_3") (pintype "power_in"))
      (node (ref "LED31") (pin "3") (pinfunction "VSS_3") (pintype "power_in"))
      (node (ref "LED32") (pin "3") (pinfunction "VSS_3") (pintype "power_in"))
      (node (ref "LED33") (pin "3") (pinfunction "VSS_3") (pintype "power_in"))
      (node (ref "LED34") (pin "3") (pinfunction "VSS_3") (pintype "power_in"))
      (node (ref "LED35") (pin "3") (pinfunction "VSS_3") (pintype "power_in"))
      (node (ref "LED36") (pin "3") (pinfunction "VSS_3") (pintype "power_in"))
      (node (ref "LED4") (pin "3") (pinfunction "VSS_3") (pintype "power_in"))
      (node (ref "LED5") (pin "3") (pinfunction "VSS_3") (pintype "power_in"))
      (node (ref "LED6") (pin "3") (pinfunction "VSS_3") (pintype "power_in"))
      (node (ref "LED7") (pin "3") (pinfunction "VSS_3") (pintype "power_in"))
      (node (ref "LED8") (pin "3") (pinfunction "VSS_3") (pintype "power_in"))
      (node (ref "LED9") (pin "3") (pinfunction "VSS_3") (pintype "power_in"))
      (node (ref "PWR-LED") (pin "C") (pinfunction "C_C") (pintype "passive"))
      (node (ref "REG") (pin "2") (pinfunction "GND_2") (pintype "power_in"))
      (node (ref "RGB-IN1") (pin "1") (pinfunction "1_1") (pintype "passive"))
      (node (ref "RGB-IN2") (pin "1") (pinfunction "1_1") (pintype "passive"))
    )
    (net (code "45") (name "Net-(PWR-LED-PadA)") (class "Default")
      (node (ref "PWR-LED") (pin "A") (pinfunction "A_A") (pintype "passive"))
      (node (ref "RPL") (pin "1") (pinfunction "1_1") (pintype "passive"))
    )
    (net (code "46") (name "VCC") (class "Default")
      (node (ref "C1") (pin "2") (pinfunction "2_2") (pintype "passive"))
      (node (ref "C10") (pin "2") (pinfunction "2_2") (pintype "passive"))
      (node (ref "C11") (pin "2") (pinfunction "2_2") (pintype "passive"))
      (node (ref "C12") (pin "2") (pinfunction "2_2") (pintype "passive"))
      (node (ref "C13") (pin "2") (pinfunction "2_2") (pintype "passive"))
      (node (ref "C14") (pin "2") (pinfunction "2_2") (pintype "passive"))
      (node (ref "C15") (pin "2") (pinfunction "2_2") (pintype "passive"))
      (node (ref "C16") (pin "2") (pinfunction "2_2") (pintype "passive"))
      (node (ref "C17") (pin "2") (pinfunction "2_2") (pintype "passive"))
      (node (ref "C18") (pin "2") (pinfunction "2_2") (pintype "passive"))
      (node (ref "C19") (pin "2") (pinfunction "2_2") (pintype "passive"))
      (node (ref "C2") (pin "2") (pinfunction "2_2") (pintype "passive"))
      (node (ref "C20") (pin "2") (pinfunction "2_2") (pintype "passive"))
      (node (ref "C21") (pin "2") (pinfunction "2_2") (pintype "passive"))
      (node (ref "C22") (pin "2") (pinfunction "2_2") (pintype "passive"))
      (node (ref "C23") (pin "2") (pinfunction "2_2") (pintype "passive"))
      (node (ref "C24") (pin "2") (pinfunction "2_2") (pintype "passive"))
      (node (ref "C25") (pin "2") (pinfunction "2_2") (pintype "passive"))
      (node (ref "C26") (pin "2") (pinfunction "2_2") (pintype "passive"))
      (node (ref "C27") (pin "2") (pinfunction "2_2") (pintype "passive"))
      (node (ref "C28") (pin "2") (pinfunction "2_2") (pintype "passive"))
      (node (ref "C29") (pin "2") (pinfunction "2_2") (pintype "passive"))
      (node (ref "C3") (pin "2") (pinfunction "2_2") (pintype "passive"))
      (node (ref "C30") (pin "2") (pinfunction "2_2") (pintype "passive"))
      (node (ref "C31") (pin "2") (pinfunction "2_2") (pintype "passive"))
      (node (ref "C32") (pin "2") (pinfunction "2_2") (pintype "passive"))
      (node (ref "C33") (pin "2") (pinfunction "2_2") (pintype "passive"))
      (node (ref "C34") (pin "2") (pinfunction "2_2") (pintype "passive"))
      (node (ref "C35") (pin "2") (pinfunction "2_2") (pintype "passive"))
      (node (ref "C36") (pin "2") (pinfunction "2_2") (pintype "passive"))
      (node (ref "C37") (pin "2") (pinfunction "2_2") (pintype "passive"))
      (node (ref "C38") (pin "2") (pinfunction "2_2") (pintype "passive"))
      (node (ref "C4") (pin "2") (pinfunction "2_2") (pintype "passive"))
      (node (ref "C5") (pin "2") (pinfunction "2_2") (pintype "passive"))
      (node (ref "C6") (pin "2") (pinfunction "2_2") (pintype "passive"))
      (node (ref "C7") (pin "2") (pinfunction "2_2") (pintype "passive"))
      (node (ref "C8") (pin "2") (pinfunction "2_2") (pintype "passive"))
      (node (ref "C9") (pin "2") (pinfunction "2_2") (pintype "passive"))
      (node (ref "JSG2") (pin "2") (pinfunction "2_2") (pintype "passive"))
      (node (ref "LED1") (pin "1") (pinfunction "VDD_1") (pintype "power_in"))
      (node (ref "LED10") (pin "1") (pinfunction "VDD_1") (pintype "power_in"))
      (node (ref "LED11") (pin "1") (pinfunction "VDD_1") (pintype "power_in"))
      (node (ref "LED12") (pin "1") (pinfunction "VDD_1") (pintype "power_in"))
      (node (ref "LED13") (pin "1") (pinfunction "VDD_1") (pintype "power_in"))
      (node (ref "LED14") (pin "1") (pinfunction "VDD_1") (pintype "power_in"))
      (node (ref "LED15") (pin "1") (pinfunction "VDD_1") (pintype "power_in"))
      (node (ref "LED16") (pin "1") (pinfunction "VDD_1") (pintype "power_in"))
      (node (ref "LED17") (pin "1") (pinfunction "VDD_1") (pintype "power_in"))
      (node (ref "LED18") (pin "1") (pinfunction "VDD_1") (pintype "power_in"))
      (node (ref "LED19") (pin "1") (pinfunction "VDD_1") (pintype "power_in"))
      (node (ref "LED2") (pin "1") (pinfunction "VDD_1") (pintype "power_in"))
      (node (ref "LED20") (pin "1") (pinfunction "VDD_1") (pintype "power_in"))
      (node (ref "LED21") (pin "1") (pinfunction "VDD_1") (pintype "power_in"))
      (node (ref "LED22") (pin "1") (pinfunction "VDD_1") (pintype "power_in"))
      (node (ref "LED23") (pin "1") (pinfunction "VDD_1") (pintype "power_in"))
      (node (ref "LED24") (pin "1") (pinfunction "VDD_1") (pintype "power_in"))
      (node (ref "LED25") (pin "1") (pinfunction "VDD_1") (pintype "power_in"))
      (node (ref "LED26") (pin "1") (pinfunction "VDD_1") (pintype "power_in"))
      (node (ref "LED27") (pin "1") (pinfunction "VDD_1") (pintype "power_in"))
      (node (ref "LED28") (pin "1") (pinfunction "VDD_1") (pintype "power_in"))
      (node (ref "LED29") (pin "1") (pinfunction "VDD_1") (pintype "power_in"))
      (node (ref "LED3") (pin "1") (pinfunction "VDD_1") (pintype "power_in"))
      (node (ref "LED30") (pin "1") (pinfunction "VDD_1") (pintype "power_in"))
      (node (ref "LED31") (pin "1") (pinfunction "VDD_1") (pintype "power_in"))
      (node (ref "LED32") (pin "1") (pinfunction "VDD_1") (pintype "power_in"))
      (node (ref "LED33") (pin "1") (pinfunction "VDD_1") (pintype "power_in"))
      (node (ref "LED34") (pin "1") (pinfunction "VDD_1") (pintype "power_in"))
      (node (ref "LED35") (pin "1") (pinfunction "VDD_1") (pintype "power_in"))
      (node (ref "LED36") (pin "1") (pinfunction "VDD_1") (pintype "power_in"))
      (node (ref "LED4") (pin "1") (pinfunction "VDD_1") (pintype "power_in"))
      (node (ref "LED5") (pin "1") (pinfunction "VDD_1") (pintype "power_in"))
      (node (ref "LED6") (pin "1") (pinfunction "VDD_1") (pintype "power_in"))
      (node (ref "LED7") (pin "1") (pinfunction "VDD_1") (pintype "power_in"))
      (node (ref "LED8") (pin "1") (pinfunction "VDD_1") (pintype "power_in"))
      (node (ref "LED9") (pin "1") (pinfunction "VDD_1") (pintype "power_in"))
      (node (ref "RPL") (pin "2") (pinfunction "2_2") (pintype "passive"))
      (node (ref "SJ1") (pin "2") (pinfunction "2_2") (pintype "passive"))
    )
  )
)
